# Power.net
KiCad netlist of a schematic drawn in Altium Designer
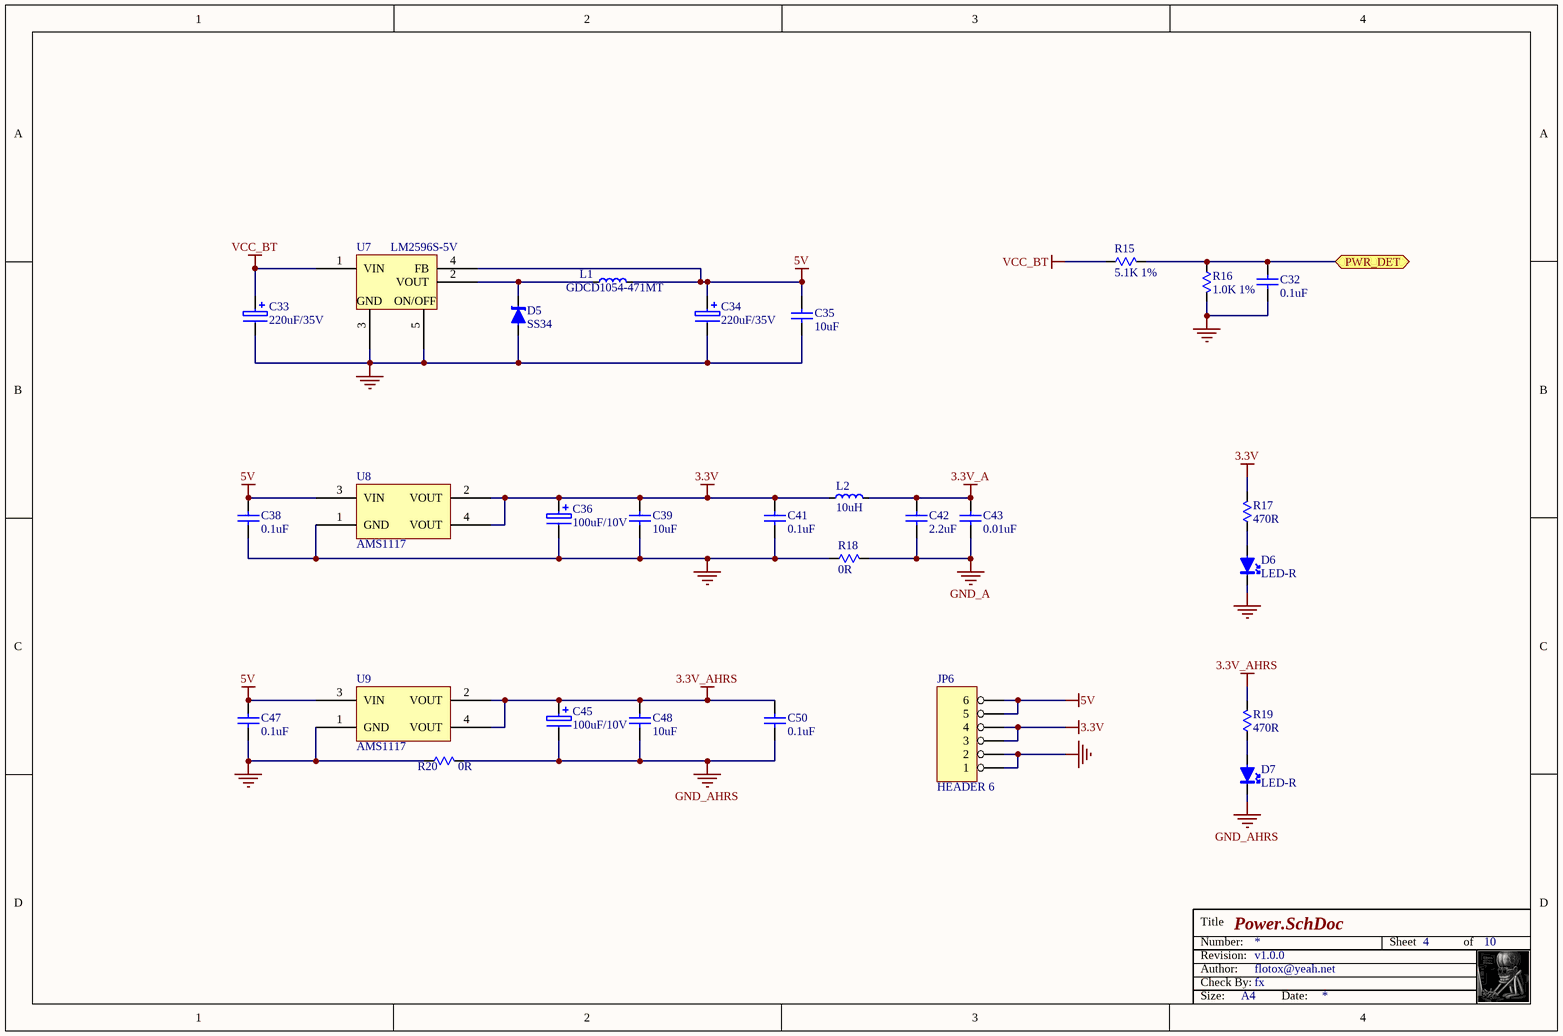
[diagram p0: Power.SchDoc]

(export (version "E")
  (design (tool "Eeschema 10.0.6"))
  (components
    (comp (ref "C32")
      (value "0.1uF")
      (footprint "C0603-S")
      (description "Capacitor")
      (libsource (lib "Passive Components Class") (part "CAP"))
    )
    (comp (ref "C33")
      (value "220uF/35V")
      (footprint "CAPPR-8.3X8.3-SM-F")
      (description "Polarized Capacitor")
      (libsource (lib "Passive Components Class") (part "CAP-ELEC"))
    )
    (comp (ref "C34")
      (value "220uF/35V")
      (footprint "CAPPR-8.3X8.3-SM-F")
      (description "Polarized Capacitor")
      (libsource (lib "Passive Components Class") (part "CAP-ELEC"))
    )
    (comp (ref "C35")
      (value "10uF")
      (footprint "C0603-S")
      (description "Capacitor")
      (libsource (lib "Passive Components Class") (part "CAP"))
    )
    (comp (ref "C36")
      (value "100uF/10V")
      (footprint "CAPPR-5.3X5.3-SM-C")
      (description "Polarized Capacitor")
      (libsource (lib "Passive Components Class") (part "CAP-ELEC"))
    )
    (comp (ref "C38")
      (value "0.1uF")
      (footprint "C0603-S")
      (description "Capacitor")
      (libsource (lib "Passive Components Class") (part "CAP"))
    )
    (comp (ref "C39")
      (value "10uF")
      (footprint "C0603-S")
      (description "Capacitor")
      (libsource (lib "Passive Components Class") (part "CAP"))
    )
    (comp (ref "C41")
      (value "0.1uF")
      (footprint "C0603-S")
      (description "Capacitor")
      (libsource (lib "Passive Components Class") (part "CAP"))
    )
    (comp (ref "C42")
      (value "2.2uF")
      (footprint "C0603-S")
      (description "Capacitor")
      (libsource (lib "Passive Components Class") (part "CAP"))
    )
    (comp (ref "C43")
      (value "0.01uF")
      (footprint "C0603-S")
      (description "Capacitor")
      (libsource (lib "Passive Components Class") (part "CAP"))
    )
    (comp (ref "C45")
      (value "100uF/10V")
      (footprint "CAPPR-5.3X5.3-SM-C")
      (description "Polarized Capacitor")
      (libsource (lib "Passive Components Class") (part "CAP-ELEC"))
    )
    (comp (ref "C47")
      (value "0.1uF")
      (footprint "C0603-S")
      (description "Capacitor")
      (libsource (lib "Passive Components Class") (part "CAP"))
    )
    (comp (ref "C48")
      (value "10uF")
      (footprint "C0603-S")
      (description "Capacitor")
      (libsource (lib "Passive Components Class") (part "CAP"))
    )
    (comp (ref "C50")
      (value "0.1uF")
      (footprint "C0603-S")
      (description "Capacitor")
      (libsource (lib "Passive Components Class") (part "CAP"))
    )
    (comp (ref "D5")
      (value "SS34")
      (footprint "SMB")
      (description "Schottky barrier rectifier")
      (libsource (lib "Passive Components Class") (part "DIODE-SBD"))
    )
    (comp (ref "D6")
      (value "LED-R")
      (footprint "LED0603")
      (description "Light Emitting Diode")
      (libsource (lib "Passive Components Class") (part "LED"))
    )
    (comp (ref "D7")
      (value "LED-R")
      (footprint "LED0603")
      (description "Light Emitting Diode")
      (libsource (lib "Passive Components Class") (part "LED"))
    )
    (comp (ref "JP6")
      (value "HEADER 6")
      (footprint "WHDR2.0X6")
      (libsource (lib "Connector Class") (part "HEADER 6"))
    )
    (comp (ref "L1")
      (value "GDCD1054-471MT")
      (footprint "GDCD1054")
      (description "Inductor")
      (libsource (lib "Passive Components Class") (part "INDUCT"))
    )
    (comp (ref "L2")
      (value "10uH")
      (footprint "L0603-C")
      (description "Inductor")
      (libsource (lib "Passive Components Class") (part "INDUCT"))
    )
    (comp (ref "R15")
      (value "5.1K 1%")
      (footprint "R0603-S")
      (description "Resistor")
      (libsource (lib "Passive Components Class") (part "RES"))
    )
    (comp (ref "R16")
      (value "1.0K 1%")
      (footprint "R0603-S")
      (description "Resistor")
      (libsource (lib "Passive Components Class") (part "RES"))
    )
    (comp (ref "R17")
      (value "470R")
      (footprint "R0603-S")
      (description "Resistor")
      (libsource (lib "Passive Components Class") (part "RES"))
    )
    (comp (ref "R18")
      (value "0R")
      (footprint "R0805-S")
      (description "Resistor")
      (libsource (lib "Passive Components Class") (part "RES"))
    )
    (comp (ref "R19")
      (value "470R")
      (footprint "R0603-S")
      (description "Resistor")
      (libsource (lib "Passive Components Class") (part "RES"))
    )
    (comp (ref "R20")
      (value "0R")
      (footprint "R0805-S")
      (description "Resistor")
      (libsource (lib "Passive Components Class") (part "RES"))
    )
    (comp (ref "U7")
      (value "LM2596S-5V")
      (footprint "D2PAK")
      (libsource (lib "Power Management Class") (part "LM2596"))
    )
    (comp (ref "U8")
      (value "AMS1117")
      (footprint "SOT-223")
      (description "800mA Low-Dropout Linear Regulator")
      (libsource (lib "Power Management Class") (part "AMS1117"))
    )
    (comp (ref "U9")
      (value "AMS1117")
      (footprint "SOT-223")
      (description "800mA Low-Dropout Linear Regulator")
      (libsource (lib "Power Management Class") (part "AMS1117"))
    )
  )
  (nets
    (net (code "1") (name "/PWR_DET") (class "Default")
      (node (ref "C32") (pin "2") (pinfunction "2_2") (pintype "passive"))
      (node (ref "R15") (pin "1") (pinfunction "1_1") (pintype "passive"))
      (node (ref "R16") (pin "2") (pinfunction "2_2") (pintype "passive"))
    )
    (net (code "2") (name "3.3V") (class "Default")
      (node (ref "C36") (pin "1") (pinfunction "1_1") (pintype "passive"))
      (node (ref "C39") (pin "2") (pinfunction "2_2") (pintype "passive"))
      (node (ref "C41") (pin "2") (pinfunction "2_2") (pintype "passive"))
      (node (ref "JP6") (pin "3") (pinfunction "3_3") (pintype "passive"))
      (node (ref "JP6") (pin "4") (pinfunction "4_4") (pintype "passive"))
      (node (ref "L2") (pin "1") (pinfunction "1_1") (pintype "passive"))
      (node (ref "R17") (pin "1") (pinfunction "1_1") (pintype "passive"))
      (node (ref "U8") (pin "2") (pinfunction "VOUT_2") (pintype "passive"))
      (node (ref "U8") (pin "4") (pinfunction "VOUT_4") (pintype "passive"))
    )
    (net (code "3") (name "3.3V_A") (class "Default")
      (node (ref "C42") (pin "2") (pinfunction "2_2") (pintype "passive"))
      (node (ref "C43") (pin "2") (pinfunction "2_2") (pintype "passive"))
      (node (ref "L2") (pin "2") (pinfunction "2_2") (pintype "passive"))
    )
    (net (code "4") (name "3.3V_AHRS") (class "Default")
      (node (ref "C45") (pin "1") (pinfunction "1_1") (pintype "passive"))
      (node (ref "C48") (pin "2") (pinfunction "2_2") (pintype "passive"))
      (node (ref "C50") (pin "2") (pinfunction "2_2") (pintype "passive"))
      (node (ref "R19") (pin "1") (pinfunction "1_1") (pintype "passive"))
      (node (ref "U9") (pin "2") (pinfunction "VOUT_2") (pintype "passive"))
      (node (ref "U9") (pin "4") (pinfunction "VOUT_4") (pintype "passive"))
    )
    (net (code "5") (name "5V") (class "Default")
      (node (ref "C34") (pin "1") (pinfunction "1_1") (pintype "passive"))
      (node (ref "C35") (pin "2") (pinfunction "2_2") (pintype "passive"))
      (node (ref "C38") (pin "2") (pinfunction "2_2") (pintype "passive"))
      (node (ref "C47") (pin "2") (pinfunction "2_2") (pintype "passive"))
      (node (ref "JP6") (pin "5") (pinfunction "5_5") (pintype "passive"))
      (node (ref "JP6") (pin "6") (pinfunction "6_6") (pintype "passive"))
      (node (ref "L1") (pin "2") (pinfunction "2_2") (pintype "passive"))
      (node (ref "U7") (pin "4") (pinfunction "FB_4") (pintype "passive"))
      (node (ref "U8") (pin "3") (pinfunction "VIN_3") (pintype "passive"))
      (node (ref "U9") (pin "3") (pinfunction "VIN_3") (pintype "passive"))
    )
    (net (code "6") (name "GND") (class "Default")
      (node (ref "C32") (pin "1") (pinfunction "1_1") (pintype "passive"))
      (node (ref "C33") (pin "2") (pinfunction "2_2") (pintype "passive"))
      (node (ref "C34") (pin "2") (pinfunction "2_2") (pintype "passive"))
      (node (ref "C35") (pin "1") (pinfunction "1_1") (pintype "passive"))
      (node (ref "C36") (pin "2") (pinfunction "2_2") (pintype "passive"))
      (node (ref "C38") (pin "1") (pinfunction "1_1") (pintype "passive"))
      (node (ref "C39") (pin "1") (pinfunction "1_1") (pintype "passive"))
      (node (ref "C41") (pin "1") (pinfunction "1_1") (pintype "passive"))
      (node (ref "C47") (pin "1") (pinfunction "1_1") (pintype "passive"))
      (node (ref "D5") (pin "1") (pinfunction "A_1") (pintype "passive"))
      (node (ref "D6") (pin "2") (pinfunction "K_2") (pintype "passive"))
      (node (ref "JP6") (pin "1") (pinfunction "1_1") (pintype "passive"))
      (node (ref "JP6") (pin "2") (pinfunction "2_2") (pintype "passive"))
      (node (ref "R16") (pin "1") (pinfunction "1_1") (pintype "passive"))
      (node (ref "R18") (pin "2") (pinfunction "2_2") (pintype "passive"))
      (node (ref "R20") (pin "2") (pinfunction "2_2") (pintype "passive"))
      (node (ref "U7") (pin "3") (pinfunction "GND_3") (pintype "passive"))
      (node (ref "U7") (pin "5") (pinfunction "ON/OFF_5") (pintype "passive"))
      (node (ref "U8") (pin "1") (pinfunction "GND_1") (pintype "passive"))
      (node (ref "U9") (pin "1") (pinfunction "GND_1") (pintype "passive"))
    )
    (net (code "7") (name "GND_A") (class "Default")
      (node (ref "C42") (pin "1") (pinfunction "1_1") (pintype "passive"))
      (node (ref "C43") (pin "1") (pinfunction "1_1") (pintype "passive"))
      (node (ref "R18") (pin "1") (pinfunction "1_1") (pintype "passive"))
    )
    (net (code "8") (name "GND_AHRS") (class "Default")
      (node (ref "C45") (pin "2") (pinfunction "2_2") (pintype "passive"))
      (node (ref "C48") (pin "1") (pinfunction "1_1") (pintype "passive"))
      (node (ref "C50") (pin "1") (pinfunction "1_1") (pintype "passive"))
      (node (ref "D7") (pin "2") (pinfunction "K_2") (pintype "passive"))
      (node (ref "R20") (pin "1") (pinfunction "1_1") (pintype "passive"))
    )
    (net (code "9") (name "Net-(D5-K)") (class "Default")
      (node (ref "D5") (pin "2") (pinfunction "K_2") (pintype "passive"))
      (node (ref "L1") (pin "1") (pinfunction "1_1") (pintype "passive"))
      (node (ref "U7") (pin "2") (pinfunction "VOUT_2") (pintype "passive"))
    )
    (net (code "10") (name "Net-(D6-A)") (class "Default")
      (node (ref "D6") (pin "1") (pinfunction "A_1") (pintype "passive"))
      (node (ref "R17") (pin "2") (pinfunction "2_2") (pintype "passive"))
    )
    (net (code "11") (name "Net-(D7-A)") (class "Default")
      (node (ref "D7") (pin "1") (pinfunction "A_1") (pintype "passive"))
      (node (ref "R19") (pin "2") (pinfunction "2_2") (pintype "passive"))
    )
    (net (code "12") (name "VCC_BT") (class "Default")
      (node (ref "C33") (pin "1") (pinfunction "1_1") (pintype "passive"))
      (node (ref "R15") (pin "2") (pinfunction "2_2") (pintype "passive"))
      (node (ref "U7") (pin "1") (pinfunction "VIN_1") (pintype "passive"))
    )
  )
)
